# SparkFun_LilyPad_Coincell-Battery.net
KiCad netlist of a schematic drawn in EAGLE
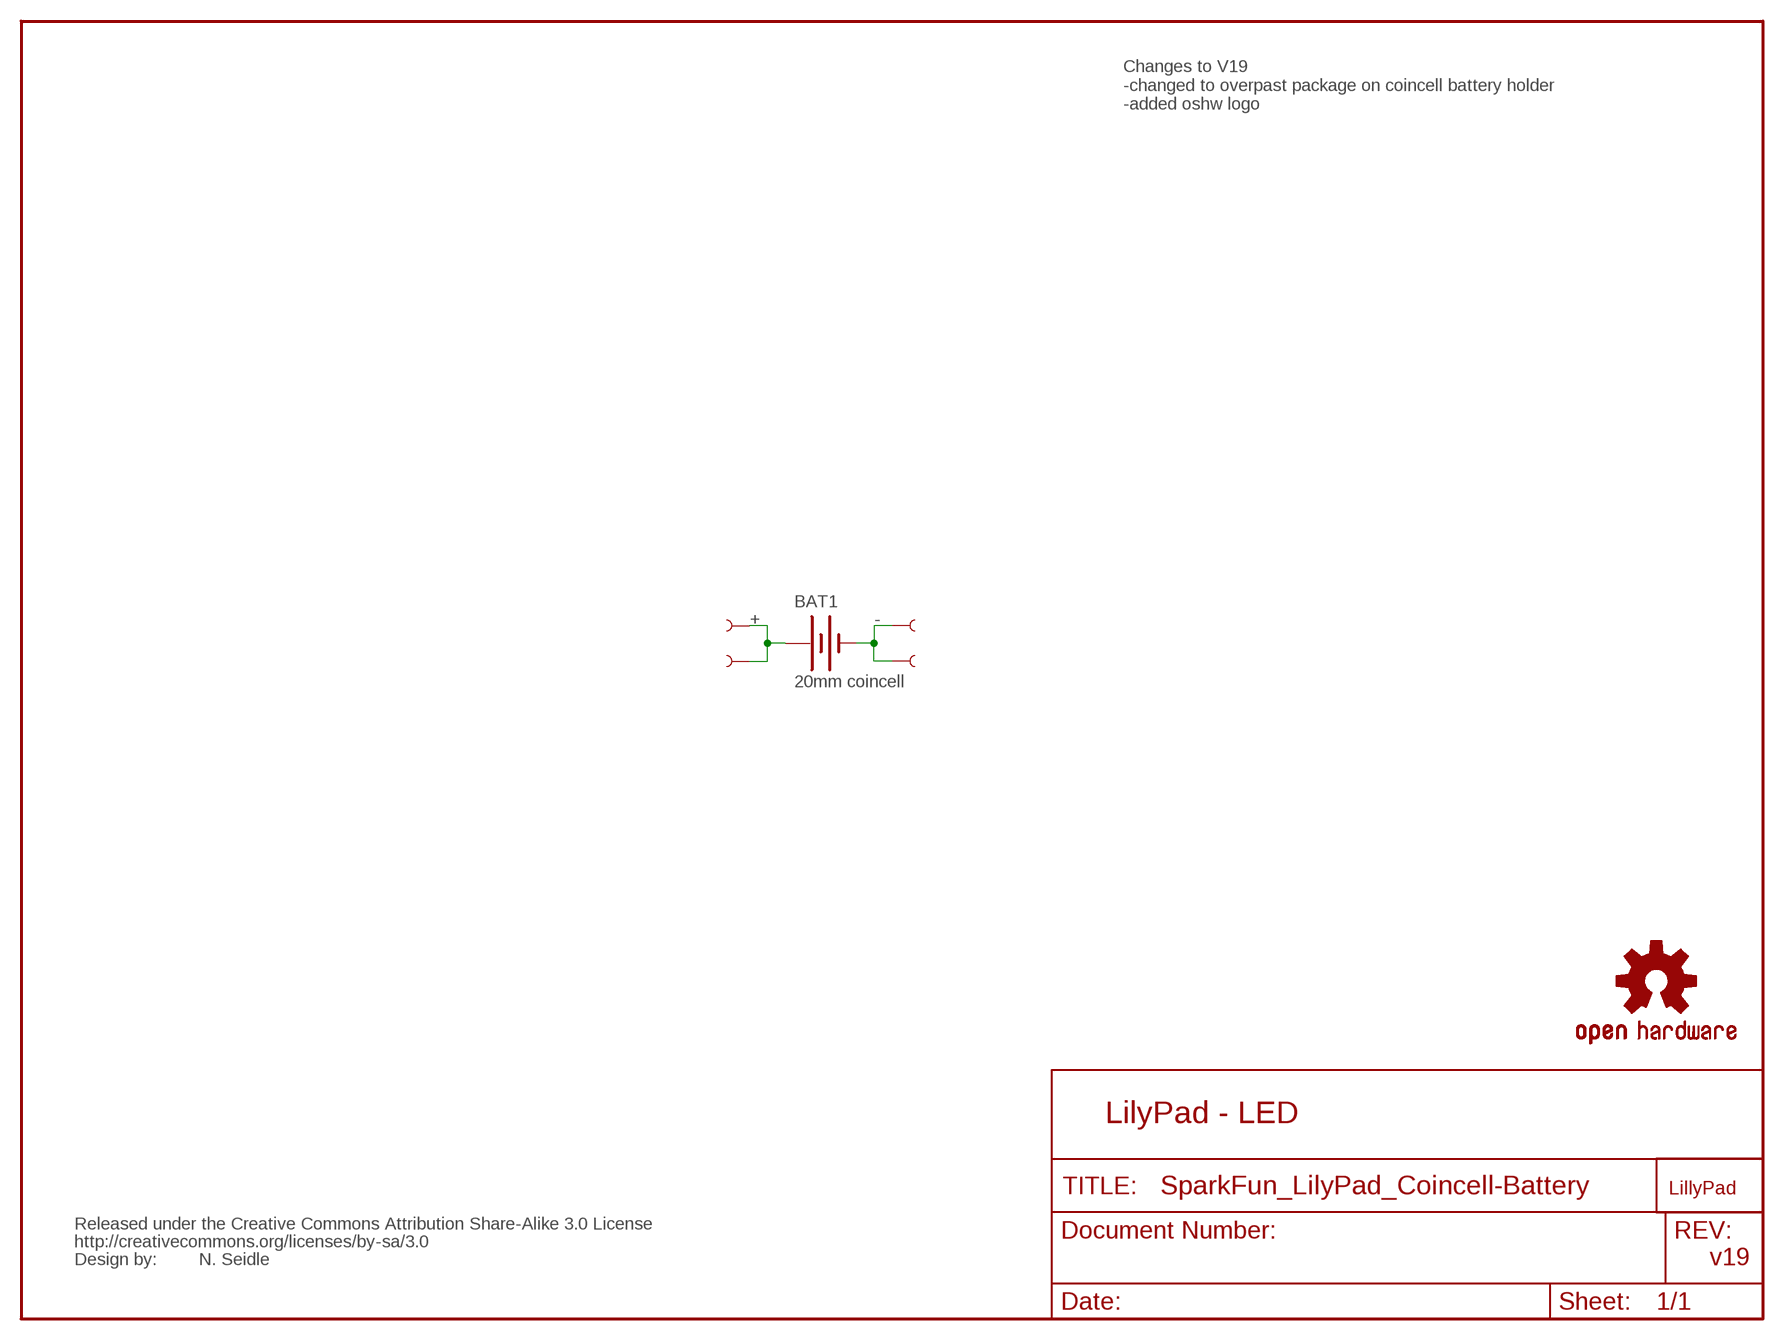
[diagram p0: schematic, sheet 1]

(export (version "E")
  (design (tool "Eeschema 10.0.6"))
  (components
    (comp (ref "BAT1")
      (value "20mm coincell")
      (footprint "eagle-import:BATTCON_20MM_4LEGS_OVERPASTE")
      (libsource (lib "eagle-import") (part "BATTERY20MM_4LEGS_OVERPASTE"))
    )
    (comp (ref "U$1")
      (value "SEWTAP6")
      (footprint "eagle-import:PETAL-SMALL-2SIDE")
      (libsource (lib "eagle-import") (part "SEWTAP6"))
    )
    (comp (ref "U$2")
      (value "SEWTAP6")
      (footprint "eagle-import:PETAL-SMALL-2SIDE")
      (libsource (lib "eagle-import") (part "SEWTAP6"))
    )
    (comp (ref "U$3")
      (value "SEWTAP6")
      (footprint "eagle-import:PETAL-SMALL-2SIDE")
      (libsource (lib "eagle-import") (part "SEWTAP6"))
    )
    (comp (ref "U$4")
      (value "SEWTAP6")
      (footprint "eagle-import:PETAL-SMALL-2SIDE")
      (libsource (lib "eagle-import") (part "SEWTAP6"))
    )
    (comp (ref "U$5")
      (value "LOGO-LPLP")
      (footprint "eagle-import:LOGO-LILYPAD")
      (libsource (lib "eagle-import") (part "LOGO-LPLP"))
    )
    (comp (ref "U$6")
      (value "CREATIVE_COMMONS")
      (footprint "eagle-import:CREATIVE_COMMONS")
      (libsource (lib "eagle-import") (part "CREATIVE_COMMONS"))
    )
    (comp (ref "U$7")
      (value "OSHW-LOGOS")
      (footprint "eagle-import:OSHW-LOGO-S")
      (libsource (lib "eagle-import") (part "OSHW-LOGOS"))
    )
  )
  (nets
    (net (code "1") (name "/+") (class "Default")
      (node (ref "BAT1") (pin "1") (pinfunction "+_1") (pintype "power_in"))
      (node (ref "U$2") (pin "1") (pinfunction "1_1") (pintype "bidirectional"))
      (node (ref "U$4") (pin "1") (pinfunction "1_1") (pintype "bidirectional"))
    )
    (net (code "2") (name "/-") (class "Default")
      (node (ref "BAT1") (pin "2") (pinfunction "-_2") (pintype "power_in"))
      (node (ref "U$1") (pin "1") (pinfunction "1_1") (pintype "bidirectional"))
      (node (ref "U$3") (pin "1") (pinfunction "1_1") (pintype "bidirectional"))
    )
  )
)
